# ESP8266-01_Solid_State_Relay_2016-01-18b.net
KiCad netlist of a schematic drawn in EAGLE
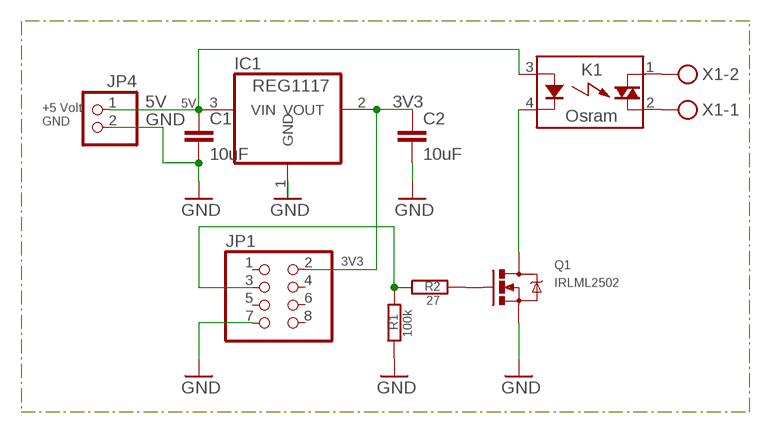
[diagram p0: schematic, sheet 1]

(export (version "E")
  (design (tool "Eeschema 10.0.6"))
  (components
    (comp (ref "C1")
      (value "10uF")
      (footprint "eagle-import:C1206")
      (libsource (lib "eagle-import") (part "C-EUC1206"))
    )
    (comp (ref "C2")
      (value "10uF")
      (footprint "eagle-import:C1206")
      (libsource (lib "eagle-import") (part "C-EUC1206"))
    )
    (comp (ref "IC1")
      (value "REG1117")
      (footprint "eagle-import:SOT223")
      (libsource (lib "eagle-import") (part "REG1117"))
    )
    (comp (ref "JP1")
      (value "PINHD-2X4")
      (footprint "eagle-import:2X04")
      (libsource (lib "eagle-import") (part "PINHD-2X4"))
    )
    (comp (ref "JP4")
      (value "PINHD-1X2")
      (footprint "eagle-import:1X02")
      (libsource (lib "eagle-import") (part "PINHD-1X2"))
    )
    (comp (ref "K1")
      (value "Osram")
      (footprint "eagle-import:S2XXEX")
      (libsource (lib "eagle-import") (part "S202SE1"))
    )
    (comp (ref "Q1")
      (value "IRLML2502")
      (footprint "eagle-import:SOT23-3")
      (libsource (lib "eagle-import") (part "MOSFET-NCHANNELAO3404A"))
    )
    (comp (ref "R1")
      (value "100k")
      (footprint "eagle-import:R0805")
      (libsource (lib "eagle-import") (part "R-EU_R0805"))
    )
    (comp (ref "R2")
      (value "27")
      (footprint "eagle-import:R0805")
      (libsource (lib "eagle-import") (part "R-EU_R0805"))
    )
    (comp (ref "X1")
      (value "W237-102")
      (footprint "eagle-import:W237-102")
      (fields (field (name "MPN") "237-102"))
      (libsource (lib "eagle-import") (part "W237-102"))
    )
  )
  (nets
    (net (code "1") (name "/3V3") (class "Default")
      (node (ref "C2") (pin "1") (pinfunction "1_1") (pintype "passive"))
      (node (ref "IC1") (pin "2") (pinfunction "VOUT_2") (pintype "output"))
      (node (ref "JP1") (pin "2") (pinfunction "2_2") (pintype "passive"))
    )
    (net (code "2") (name "/5V") (class "Default")
      (node (ref "C1") (pin "1") (pinfunction "1_1") (pintype "passive"))
      (node (ref "IC1") (pin "3") (pinfunction "VIN_3") (pintype "input"))
      (node (ref "JP4") (pin "1") (pinfunction "1_1") (pintype "passive"))
      (node (ref "K1") (pin "3") (pinfunction "A_3") (pintype "passive"))
    )
    (net (code "3") (name "GND") (class "Default")
      (node (ref "C1") (pin "2") (pinfunction "2_2") (pintype "passive"))
      (node (ref "C2") (pin "2") (pinfunction "2_2") (pintype "passive"))
      (node (ref "IC1") (pin "1") (pinfunction "GND_1") (pintype "power_in"))
      (node (ref "JP1") (pin "7") (pinfunction "7_7") (pintype "passive"))
      (node (ref "JP4") (pin "2") (pinfunction "2_2") (pintype "passive"))
      (node (ref "Q1") (pin "2") (pinfunction "S_2") (pintype "passive"))
      (node (ref "R1") (pin "1") (pinfunction "1_1") (pintype "passive"))
    )
    (net (code "4") (name "Net-(JP1-Pad3)") (class "Default")
      (node (ref "JP1") (pin "3") (pinfunction "3_3") (pintype "passive"))
      (node (ref "R1") (pin "2") (pinfunction "2_2") (pintype "passive"))
      (node (ref "R2") (pin "1") (pinfunction "1_1") (pintype "passive"))
    )
    (net (code "5") (name "Net-(K1-DS1)") (class "Default")
      (node (ref "K1") (pin "1") (pinfunction "DS1_1") (pintype "passive"))
      (node (ref "X1") (pin "2") (pinfunction "KL_2") (pintype "passive"))
    )
    (net (code "6") (name "Net-(K1-DS2)") (class "Default")
      (node (ref "K1") (pin "2") (pinfunction "DS2_2") (pintype "passive"))
      (node (ref "X1") (pin "1") (pinfunction "KL_1") (pintype "passive"))
    )
    (net (code "7") (name "Net-(K1-K)") (class "Default")
      (node (ref "K1") (pin "4") (pinfunction "K_4") (pintype "passive"))
      (node (ref "Q1") (pin "3") (pinfunction "D_3") (pintype "passive"))
    )
    (net (code "8") (name "Net-(Q1-G)") (class "Default")
      (node (ref "Q1") (pin "1") (pinfunction "G_1") (pintype "passive"))
      (node (ref "R2") (pin "2") (pinfunction "2_2") (pintype "passive"))
    )
    (net (code "9") (name "unconnected-(JP1-Pad1)") (class "Default")
      (node (ref "JP1") (pin "1") (pinfunction "1_1") (pintype "passive"))
    )
    (net (code "10") (name "unconnected-(JP1-Pad4)") (class "Default")
      (node (ref "JP1") (pin "4") (pinfunction "4_4") (pintype "passive"))
    )
    (net (code "11") (name "unconnected-(JP1-Pad5)") (class "Default")
      (node (ref "JP1") (pin "5") (pinfunction "5_5") (pintype "passive"))
    )
    (net (code "12") (name "unconnected-(JP1-Pad6)") (class "Default")
      (node (ref "JP1") (pin "6") (pinfunction "6_6") (pintype "passive"))
    )
    (net (code "13") (name "unconnected-(JP1-Pad8)") (class "Default")
      (node (ref "JP1") (pin "8") (pinfunction "8_8") (pintype "passive"))
    )
  )
)
